# MainPower.net
KiCad netlist of a schematic drawn in Altium Designer
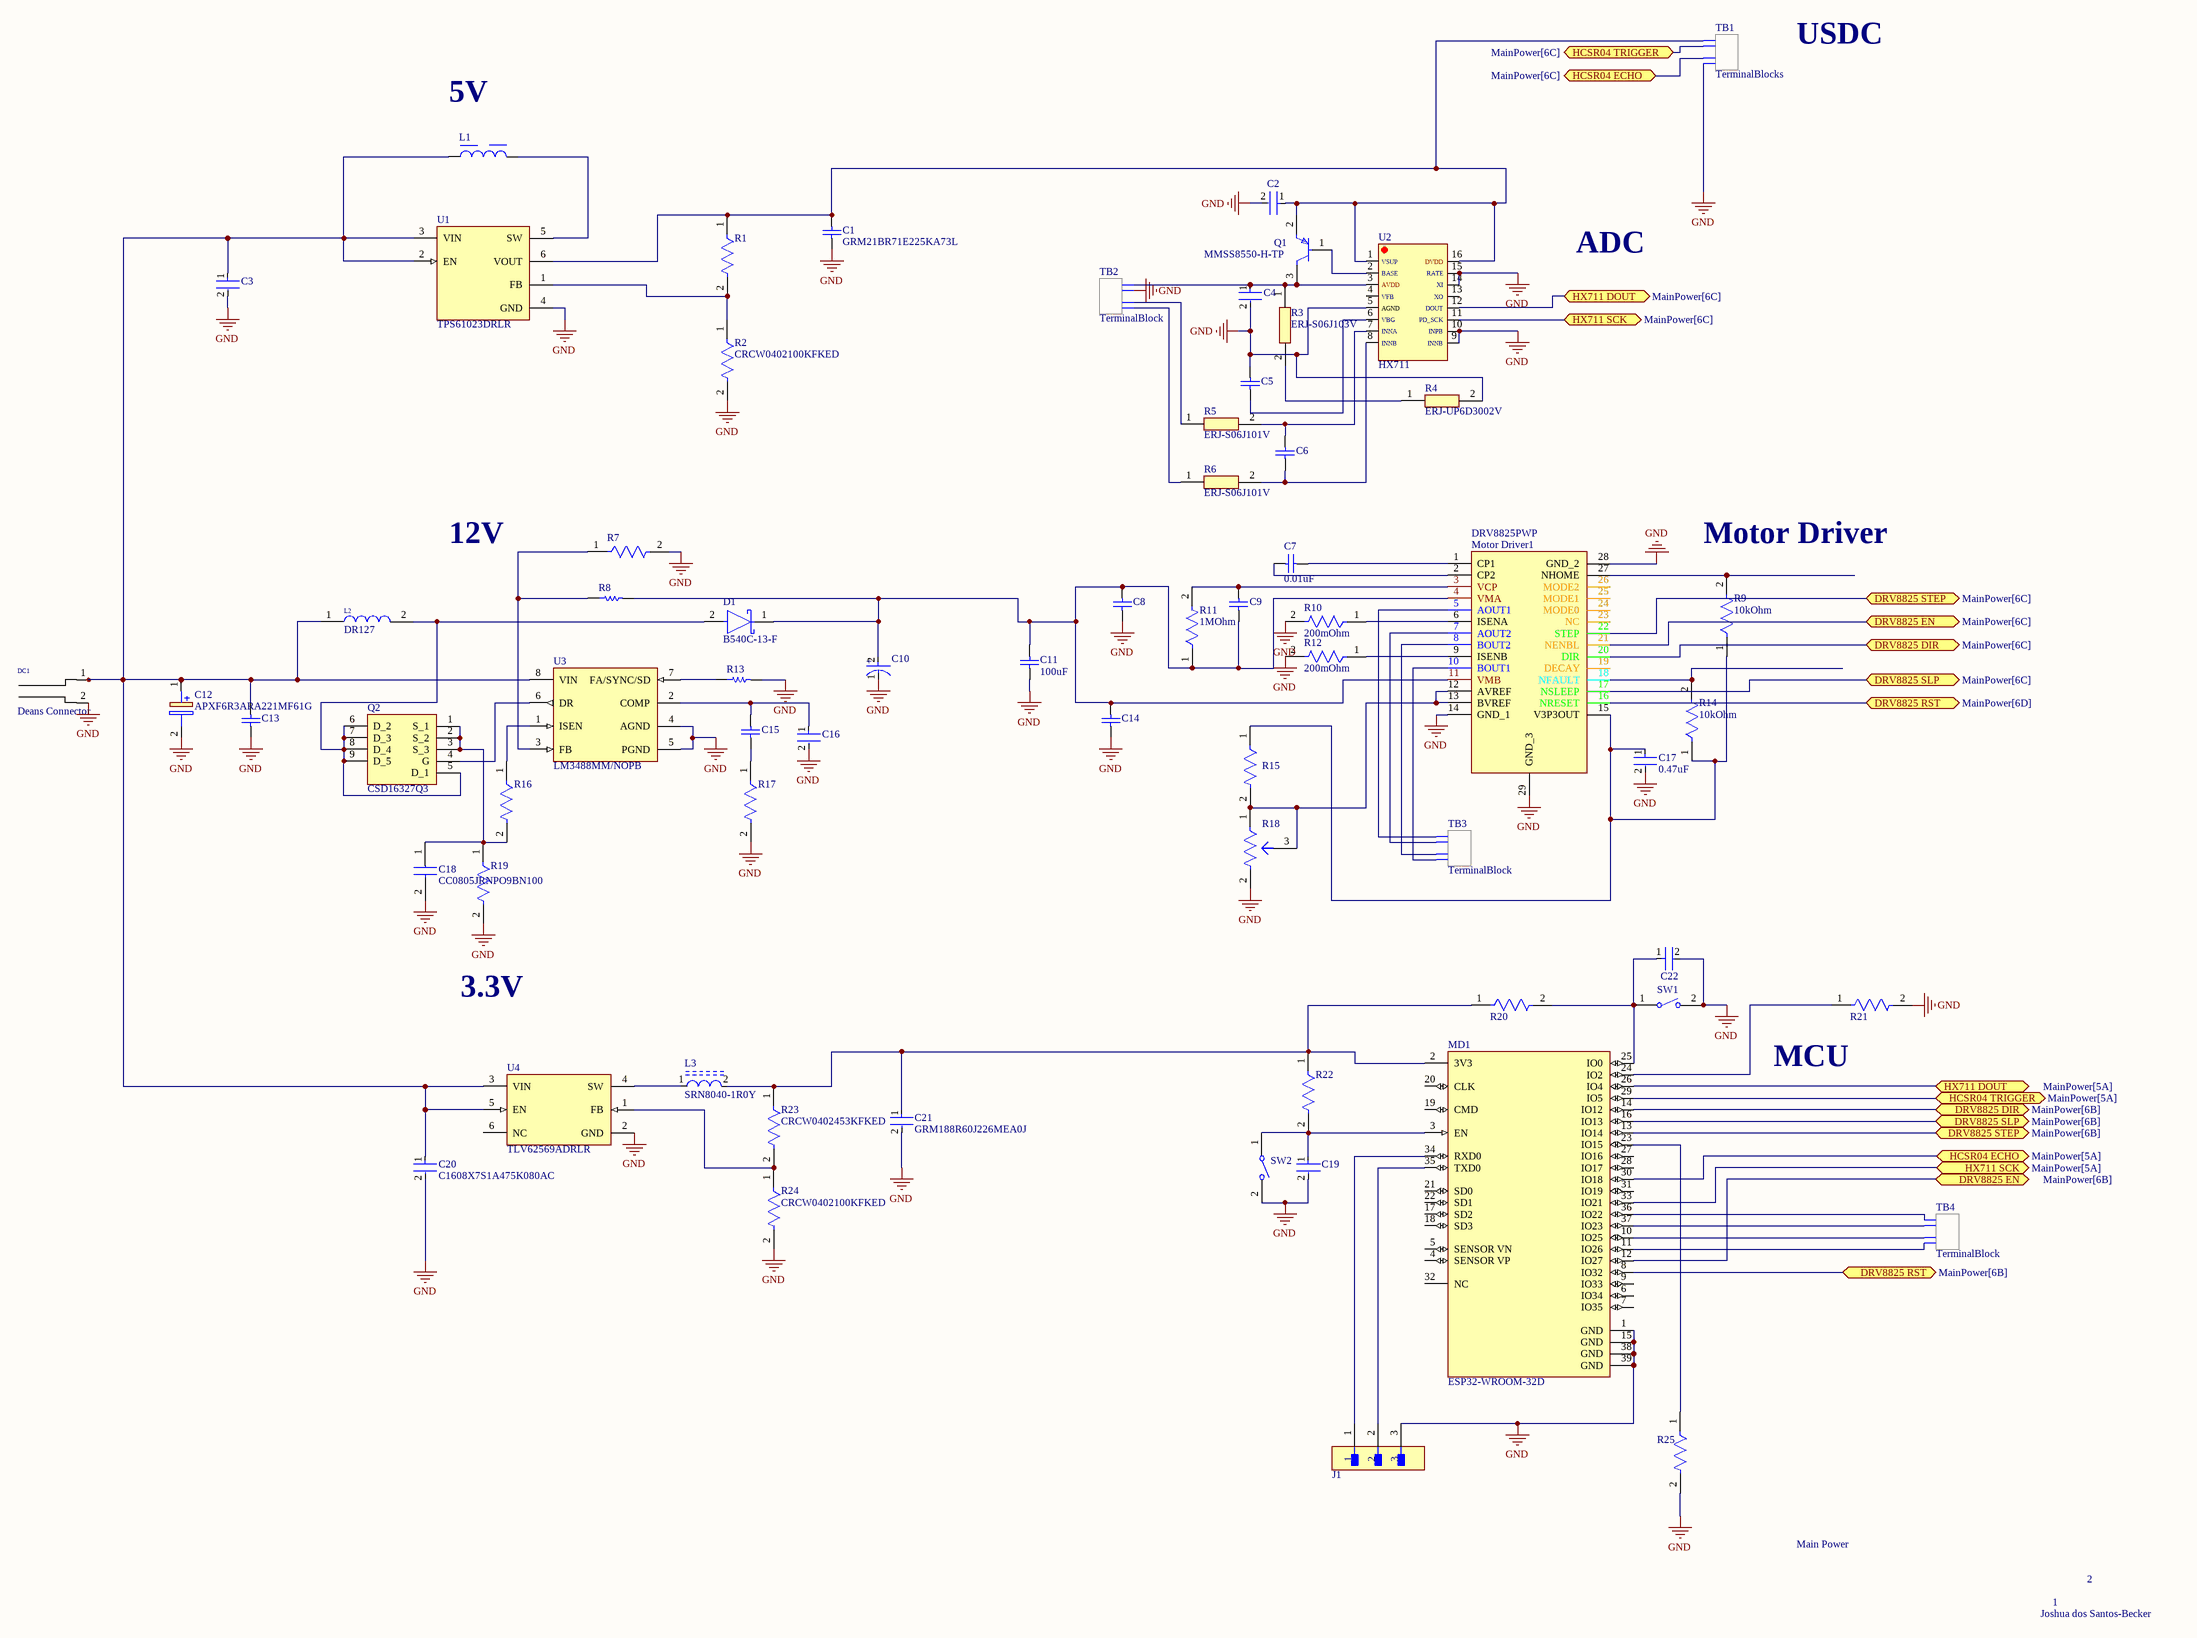
[diagram p0: MainPower.SchDoc]

(export (version "E")
  (design (tool "Eeschema 10.0.6"))
  (components
    (comp (ref "C1")
      (value "GRM21BR71E225KA73L")
      (footprint "CAPC2013X140X45NL15T25")
      (fields (field (name "MANUFACTURER") "Murata"))
      (libsource (lib "Altium Content Vault") (part "CAP"))
    )
    (comp (ref "C2")
      (value "GRM21BR61C106KE15L")
      (footprint "FP-GRM21B-0_1-IPC_C")
      (description "Chip Multilayer Ceramic Capacitors for General Purpose, 0805, 10uF, X5R, 15%, 10%, 16V")
      (fields (field (name "TOLERANCE") "10%") (field (name "VOLTAGE") "16V"))
      (libsource (lib "Altium Content Vault") (part "b4654b650e69147ec39a6b967a45e02"))
    )
    (comp (ref "C3")
      (value "C0805C106K8PACTU")
      (footprint "FP-C0805C-DG-MFG")
      (description "CAP CER 10UF 10V X5R 0805")
      (fields (field (name "TOLERANCE") "10%") (field (name "MANUFACTURER") "Kemet"))
      (libsource (lib "Altium Content Vault") (part "11868f565c42a9108669ba33697ecf6"))
    )
    (comp (ref "C4")
      (value "GRM21BR61C106KE15L")
      (footprint "FP-GRM21B-0_1-IPC_C")
      (description "Chip Multilayer Ceramic Capacitors for General Purpose, 0805, 10uF, X5R, 15%, 10%, 16V")
      (fields (field (name "TOLERANCE") "10%") (field (name "VOLTAGE") "16V"))
      (libsource (lib "Altium Content Vault") (part "b4654b650e69147ec39a6b967a45e02"))
    )
    (comp (ref "C5")
      (value "GRM033C71C104KE14J")
      (footprint "CAPC0603X33N")
      (fields (field (name "MOUSER PART NUMBER") "81-GRM033C71C104KE4J"))
      (libsource (lib "gsl") (part "0.1uF"))
    )
    (comp (ref "C6")
      (value "GRM033C71C104KE14J")
      (footprint "CAPC0603X33N")
      (fields (field (name "MOUSER PART NUMBER") "81-GRM033C71C104KE4J"))
      (libsource (lib "gsl") (part "0.1uF"))
    )
    (comp (ref "C7")
      (value "0.01uF")
      (footprint "FP-C0603-030-0_03-IPC_A")
      (description "C0603X5R1C103M030BA")
      (fields (field (name "TOLERANCE") "20%"))
      (libsource (lib "gsl") (part "0.01uF"))
    )
    (comp (ref "C8")
      (value "GRM033C71C104KE14J")
      (footprint "CAPC0603X33N")
      (fields (field (name "MOUSER PART NUMBER") "81-GRM033C71C104KE4J"))
      (libsource (lib "gsl") (part "0.1uF"))
    )
    (comp (ref "C9")
      (value "GRM033C71C104KE14J")
      (footprint "CAPC0603X33N")
      (fields (field (name "MOUSER PART NUMBER") "81-GRM033C71C104KE4J"))
      (libsource (lib "gsl") (part "0.1uF"))
    )
    (comp (ref "C10")
      (value "20SVPF390M")
      (footprint "FP-OS-CON-SMT-E12-MFG")
      (description "Conductive Polymer Aluminum Solid Capacitors (OS-CON) 390uF ±20% 20V")
      (fields (field (name "VOLTAGE") "20V") (field (name "TOLERANCE") "20%"))
      (libsource (lib "Altium Content Vault") (part "a00bbbee19879c290e62620ae7e47b1"))
    )
    (comp (ref "C11")
      (value "100uF")
      (footprint "CAPC3225X279N")
      (description "1210YD107MAT2A")
      (libsource (lib "gsl") (part "100uF"))
    )
    (comp (ref "C12")
      (value "APXF6R3ARA221MF61G")
      (footprint "SamacSys:CAPAE660X610N")
      (description "Capacitor Polarised")
      (fields (field (name "MOUSER PART NUMBER") "661-APXF6R3RA221MF61"))
      (libsource (lib "*") (part "APXF6R3ARA221MF61G"))
    )
    (comp (ref "C13")
      (value "GRM155R70J104KA01D")
      (footprint "CAPC1005X55X25NL05T10")
      (fields (field (name "MANUFACTURER") "Murata"))
      (libsource (lib "Altium Content Vault") (part "CAP"))
    )
    (comp (ref "C14")
      (value "GRM033C71C104KE14J")
      (footprint "CAPC0603X33N")
      (fields (field (name "MOUSER PART NUMBER") "81-GRM033C71C104KE4J"))
      (libsource (lib "gsl") (part "0.1uF"))
    )
    (comp (ref "C15")
      (value "GRM155R71C183KA01D")
      (footprint "CAPC1005X55X25NL05T10")
      (fields (field (name "MANUFACTURER") "Murata"))
      (libsource (lib "Altium Content Vault") (part "CAP"))
    )
    (comp (ref "C16")
      (value "CC0805KRX7R9BB102")
      (footprint "FP-CC0805-0_85-MFG")
      (description "CAP CER 1000PF 50V X7R 0805")
      (fields
        (field (name "MANUFACTURER") "Yageo")
        (field (name "OCTOPART") "https://octopart.com/cc0805krx7r9bb102-yageo-39467744")
      )
      (libsource (lib "Altium Content Vault") (part "11868f565c42a9108669ba33697ecf6"))
    )
    (comp (ref "C17")
      (value "0.47uF")
      (footprint "FP-1206-L_3_2_0_2-W_1_6_0-MFG")
      (description "12065C474K4Z2A")
      (fields (field (name "TOLERANCE") "10%"))
      (libsource (lib "Altium Content Vault") (part "b4654b650e69147ec39a6b967a45e02"))
    )
    (comp (ref "C18")
      (value "CC0805JRNPO9BN100")
      (footprint "SamacSys:CAPC2012X70N")
      (description "Capacitor")
      (fields (field (name "MOUSER PART NUMBER") "603-CC805JRNPO9BN100"))
      (libsource (lib "*") (part "CC0805JRNPO9BN100"))
    )
    (comp (ref "C19")
      (value "08055C104J4T2A")
      (footprint "FP-0805-L_2_01_0_2-W_1_25-MFG")
      (description "Automotive Ceramic Capacitor, 0805, 100nF, 5%, X7R, 15%, 50V")
      (fields (field (name "TOLERANCE") "5%"))
      (libsource (lib "Altium Content Vault") (part "02cd4be3c70576c341d710602a673aa"))
    )
    (comp (ref "C20")
      (value "C1608X7S1A475K080AC")
      (footprint "FP-C1608-080-MFG")
      (description "CAP CER 4.7UF 10V X7S 0603")
      (fields (field (name "TOLERANCE") "10%"))
      (libsource (lib "Altium Content Vault") (part "b4654b650e69147ec39a6b967a45e02"))
    )
    (comp (ref "C21")
      (value "GRM188R60J226MEA0J")
      (footprint "FP-GRM188-0_2-IPC_C")
      (description "Chip Multilayer Ceramic Capacitors for General Purpose, 0603, 22uF, X5R, 15%, 20%, 6.3V")
      (fields (field (name "TOLERANCE") "20%"))
      (libsource (lib "Altium Content Vault") (part "11868f565c42a9108669ba33697ecf6"))
    )
    (comp (ref "C22")
      (value "08055C104J4T2A")
      (footprint "FP-0805-L_2_01_0_2-W_1_25-MFG")
      (description "Automotive Ceramic Capacitor, 0805, 100nF, 5%, X7R, 15%, 50V")
      (fields (field (name "TOLERANCE") "5%"))
      (libsource (lib "Altium Content Vault") (part "02cd4be3c70576c341d710602a673aa"))
    )
    (comp (ref "D1")
      (value "B540C-13-F")
      (footprint "FP-SMC-MFG")
      (description "DIODE SCHOTTKY 40V 5A SMC")
      (fields
        (field (name "OCTOPART") "https://octopart.com/b540c-13-f-diodes+inc.-325873")
        (field (name "MANUFACTURER") "Diodes Inc.")
      )
      (libsource (lib "Altium Content Vault") (part "1d6ec82d83fb6aee721767c19dac4b9"))
    )
    (comp (ref "DC1")
      (value "Deans Connector")
      (footprint "Deans")
      (libsource (lib "gsl") (part "Deans Connector"))
    )
    (comp (ref "J1")
      (value "PREC003SAAN-RC")
      (footprint "FP-PREC003SAAN-RC-MFG")
      (description "PREC003SAAN-RC Conn Header Vert 3POS 2.54MM")
      (libsource (lib "Altium Content Vault") (part "0d3f023dd272f625e17a2be33dea85f"))
    )
    (comp (ref "L1")
      (value "74404043010A")
      (footprint "WE-LQS_4025")
      (description "74404043010A WE-LQS SMT Semi-Shielded Power Inductor")
      (libsource (lib "Altium Content Vault") (part "Inductor - 3"))
    )
    (comp (ref "L2") (value "DR127") (footprint "DR127") (libsource (lib "gsl") (part "DR127")))
    (comp (ref "L3")
      (value "SRN8040-1R0Y")
      (footprint "FP-SRN8040-MFG")
      (description "FIXED IND 1UH 7.8A 10 MOHM SMD")
      (fields (field (name "TOLERANCE") "30%"))
      (libsource (lib "Altium Content Vault") (part "faee11374f111f4f771645e57fa9eac"))
    )
    (comp (ref "MD1")
      (value "ESP32-WROOM-32D")
      (footprint "ESP32-WROOM-32D")
      (description "RX TXRX MOD WIFI SURFACE MOUNT")
      (libsource (lib "gsl") (part "ee866abf0b6c51247b7f5cdebf2f250"))
    )
    (comp (ref "Motor Driver1")
      (value "DRV8825PWP")
      (footprint "SOP65P640X120-29N")
      (fields (field (name "MOUSER PART NUMBER") "595-DRV8825PWP"))
      (libsource (lib "gsl") (part "DRV8825PWP"))
    )
    (comp (ref "Q1")
      (value "MMSS8550-H-TP")
      (footprint "FP-SOT-23-IPC_B")
      (description "TRANS PNP 25V 1.5A SOT23")
      (libsource (lib "Altium Content Vault") (part "0e8486ed3b47d9c69b8404ba87cf0f7"))
    )
    (comp (ref "Q2")
      (value "CSD16327Q3")
      (footprint "SamacSys:CSD16327Q3")
      (description "MOSFET (N-Channel)")
      (fields (field (name "MOUSER PART NUMBER") "595-CSD16327Q3"))
      (libsource (lib "*") (part "CSD16327Q3"))
    )
    (comp (ref "R1")
      (value "RC0603FR-07732KL")
      (footprint "FP-RC0603-0_55-IPC_A")
      (description "RES SMD 732K OHM 1% 1/10W 0603")
      (fields (field (name "TOLERANCE") "1%"))
      (libsource (lib "Altium Content Vault") (part "1029c3af85768c4190bb7ad29bc67b5"))
    )
    (comp (ref "R2")
      (value "CRCW0402100KFKED")
      (footprint "FP-CRCW0402-e3-IPC_C")
      (description "RES Thick Film, 100kΩ, 1%, 0.063W, 100ppm/°C, 0402")
      (fields (field (name "TOLERANCE") "1%"))
      (libsource (lib "Altium Content Vault") (part "1029c3af85768c4190bb7ad29bc67b5"))
    )
    (comp (ref "R3")
      (value "ERJ-S06J103V")
      (footprint "SamacSys:RESC2012X70N")
      (description "Resistor")
      (fields (field (name "MOUSER PART NUMBER") "667-ERJ-S06J103V"))
      (libsource (lib "*") (part "ERJ-S06J103V"))
    )
    (comp (ref "R4")
      (value "ERJ-UP6D3002V")
      (footprint "SamacSys:ERJUP6")
      (description "Resistor")
      (libsource (lib "*") (part "ERJ-UP6D3002V"))
    )
    (comp (ref "R5")
      (value "ERJ-S06J101V")
      (footprint "SamacSys:RESC2012X70N")
      (description "Resistor")
      (fields (field (name "MOUSER PART NUMBER") "667-ERJ-S06J101V"))
      (libsource (lib "*") (part "ERJ-S06J101V"))
    )
    (comp (ref "R6")
      (value "ERJ-S06J101V")
      (footprint "SamacSys:RESC2012X70N")
      (description "Resistor")
      (fields (field (name "MOUSER PART NUMBER") "667-ERJ-S06J101V"))
      (libsource (lib "*") (part "ERJ-S06J101V"))
    )
    (comp (ref "R7")
      (value "CRCW04021K00FKED")
      (footprint "FP-CRCW0402-e3-MFG")
      (description "RES Thick Film, 1kΩ, 1%, 0.063W, 100ppm/°C, 0402")
      (fields (field (name "TOLERANCE") "1%"))
      (libsource (lib "Altium Content Vault") (part "1029c3af85768c4190bb7ad29bc67b5"))
    )
    (comp (ref "R8")
      (value "CRCW04028K45FKED")
      (footprint "RESC1005X40X25LL05T05")
      (fields (field (name "MANUFACTURER") "Vishay Dale"))
      (libsource (lib "Altium Content Vault") (part "RES"))
    )
    (comp (ref "R9")
      (value "10kOhm")
      (footprint "FP-ESR10-IPC_C")
      (description "ESR10EZPD1002")
      (libsource (lib "Altium Content Vault") (part "1029c3af85768c4190bb7ad29bc67b5"))
    )
    (comp (ref "R10")
      (value "200mOhm")
      (footprint "WSL2512R2000FEA")
      (description "WSL2512R2000FEA")
      (libsource (lib "gsl") (part "200mOhm"))
    )
    (comp (ref "R11")
      (value "1MOhm")
      (footprint "RESC1005X40N")
      (description "CRCW04021M00FKEDHP")
      (libsource (lib "gsl") (part "1MOhm"))
    )
    (comp (ref "R12")
      (value "200mOhm")
      (footprint "WSL2512R2000FEA")
      (description "WSL2512R2000FEA")
      (libsource (lib "gsl") (part "200mOhm"))
    )
    (comp (ref "R13")
      (value "CRCW040226K1FKED")
      (footprint "RESC1005X40X25LL05T05")
      (fields (field (name "MANUFACTURER") "Vishay Dale"))
      (libsource (lib "Altium Content Vault") (part "RES"))
    )
    (comp (ref "R14")
      (value "10kOhm")
      (footprint "FP-ESR10-IPC_C")
      (description "ESR10EZPD1002")
      (libsource (lib "Altium Content Vault") (part "1029c3af85768c4190bb7ad29bc67b5"))
    )
    (comp (ref "R15")
      (value "~")
      (footprint "RESC1005X40N")
      (description "CRCW040250K0FKED")
      (libsource (lib "gsl") (part "50kOhm"))
    )
    (comp (ref "R16")
      (value "CRCW0402100RFKED")
      (footprint "FP-CRCW0402-e3-IPC_C")
      (description "RES Thick Film, 100Ω, 1%, 0.063W, 100ppm/°C, 0402")
      (fields (field (name "TOLERANCE") "1%"))
      (libsource (lib "Altium Content Vault") (part "1029c3af85768c4190bb7ad29bc67b5"))
    )
    (comp (ref "R17")
      (value "CRCW04025K11FKED")
      (footprint "FP-CRCW0402-e3-IPC_C")
      (description "RES Thick Film, 5.11kΩ, 1%, 0.063W, 100ppm/°C, 0402")
      (fields (field (name "TOLERANCE") "1%"))
      (libsource (lib "Altium Content Vault") (part "1029c3af85768c4190bb7ad29bc67b5"))
    )
    (comp (ref "R18")
      (value "~")
      (footprint "SMD Pot")
      (description "TC33X-2-303E Bourns")
      (libsource (lib "gsl") (part "30kPot"))
    )
    (comp (ref "R19")
      (value "PRL1632-R006-F-T1")
      (footprint "FP-PRL1632-MFG")
      (description "6 mOhms ±1% 1W Chip Resistor Wide 0612 (1632 Metric), Current Sense Thin Film")
      (fields (field (name "TOLERANCE") "1%"))
      (libsource (lib "Altium Content Vault") (part "1029c3af85768c4190bb7ad29bc67b5"))
    )
    (comp (ref "R20")
      (value "ESR10EZPD1002")
      (footprint "FP-ESR10-IPC_C")
      (description "10kΩ ±0.5% 0.4W 0805 Anti-Surge Chip Resistor AEC-Q200")
      (libsource (lib "Altium Content Vault") (part "1029c3af85768c4190bb7ad29bc67b5"))
    )
    (comp (ref "R21")
      (value "ESR10EZPD1002")
      (footprint "FP-ESR10-IPC_C")
      (description "10kΩ ±0.5% 0.4W 0805 Anti-Surge Chip Resistor AEC-Q200")
      (libsource (lib "Altium Content Vault") (part "1029c3af85768c4190bb7ad29bc67b5"))
    )
    (comp (ref "R22")
      (value "ESR10EZPD1002")
      (footprint "FP-ESR10-IPC_C")
      (description "10kΩ ±0.5% 0.4W 0805 Anti-Surge Chip Resistor AEC-Q200")
      (libsource (lib "Altium Content Vault") (part "1029c3af85768c4190bb7ad29bc67b5"))
    )
    (comp (ref "R23")
      (value "CRCW0402453KFKED")
      (footprint "FP-CRCW0402-e3-MFG")
      (description "RES Thick Film, 453kΩ, 1%, 0.063W, 100ppm/°C, 0402")
      (fields (field (name "TOLERANCE") "1%"))
      (libsource (lib "Altium Content Vault") (part "1029c3af85768c4190bb7ad29bc67b5"))
    )
    (comp (ref "R24")
      (value "CRCW0402100KFKED")
      (footprint "FP-CRCW0402-e3-IPC_C")
      (description "RES Thick Film, 100kΩ, 1%, 0.063W, 100ppm/°C, 0402")
      (fields (field (name "TOLERANCE") "1%"))
      (libsource (lib "Altium Content Vault") (part "1029c3af85768c4190bb7ad29bc67b5"))
    )
    (comp (ref "R25")
      (value "ESR10EZPD1002")
      (footprint "FP-ESR10-IPC_C")
      (description "10kΩ ±0.5% 0.4W 0805 Anti-Surge Chip Resistor AEC-Q200")
      (libsource (lib "Altium Content Vault") (part "1029c3af85768c4190bb7ad29bc67b5"))
    )
    (comp (ref "SW1")
      (value "FSMSM")
      (footprint "TECO-FSMSM-2_V")
      (description "FSMSM Push Button Switch, 50 mA, -35 to 85 degC, 2-Pin SMD, RoHS, Bulk")
      (fields (field (name "MANUFACTURER") "TE Connectivity"))
      (libsource (lib "Altium Content Vault") (part "SW-SPST-2_C"))
    )
    (comp (ref "SW2")
      (value "FSMSM")
      (footprint "TECO-FSMSM-2_V")
      (description "FSMSM Push Button Switch, 50 mA, -35 to 85 degC, 2-Pin SMD, RoHS, Bulk")
      (fields (field (name "MANUFACTURER") "TE Connectivity"))
      (libsource (lib "Altium Content Vault") (part "SW-SPST-2_C"))
    )
    (comp (ref "TB1")
      (value "TerminalBlocks")
      (footprint "PHOENIX_1725672")
      (libsource (lib "gsl") (part "TerminalBlock"))
    )
    (comp (ref "TB2")
      (value "TerminalBlock")
      (footprint "PHOENIX_1725672")
      (libsource (lib "") (part "TerminalBlock_1"))
    )
    (comp (ref "TB3")
      (value "TerminalBlock")
      (footprint "PHOENIX_1725672")
      (libsource (lib "gsl") (part "TerminalBlock"))
    )
    (comp (ref "TB4")
      (value "TerminalBlock")
      (footprint "PHOENIX_1725672")
      (libsource (lib "gsl") (part "TerminalBlock"))
    )
    (comp (ref "U1")
      (value "TPS61023DRLR")
      (footprint "FP-DRL0006A-MFG")
      (description "FINISH GOODS FOR TPS61023")
      (libsource (lib "Altium Content Vault") (part "b28b3e956a4ad07201ce69f9d09f9a8"))
    )
    (comp (ref "U2") (value "HX711") (footprint "TSOP127P600X160-16N") (libsource (lib "gsl") (part "HX711")))
    (comp (ref "U3")
      (value "LM3488MM/NOPB")
      (footprint "DGK0008A_M")
      (fields (field (name "MANUFACTURER") "Texas Instruments"))
      (libsource (lib "Altium Content Vault") (part "PM-SWREG-LM3488-8"))
    )
    (comp (ref "U4")
      (value "TLV62569ADRLR")
      (footprint "FP-DRL0006A-MFG")
      (description "IC REG BUCK ADJ 2A SOT563")
      (libsource (lib "Altium Content Vault") (part "c065b8f3016c1e0e14a773cb518fcf3"))
    )
  )
  (nets
    (net (code "1") (name "/DRV8825 DIR") (class "Default")
      (node (ref "MD1") (pin "14") (pinfunction "IO12_14") (pintype "bidirectional"))
      (node (ref "Motor Driver1") (pin "20") (pinfunction "DIR_20") (pintype "passive"))
    )
    (net (code "2") (name "/DRV8825 EN") (class "Default")
      (node (ref "MD1") (pin "12") (pinfunction "IO27_12") (pintype "bidirectional"))
      (node (ref "Motor Driver1") (pin "21") (pinfunction "NENBL_21") (pintype "passive"))
    )
    (net (code "3") (name "/DRV8825 RST") (class "Default")
      (node (ref "MD1") (pin "8") (pinfunction "IO32_8") (pintype "bidirectional"))
      (node (ref "Motor Driver1") (pin "16") (pinfunction "NRESET_16") (pintype "passive"))
    )
    (net (code "4") (name "/DRV8825 SLP") (class "Default")
      (node (ref "MD1") (pin "16") (pinfunction "IO13_16") (pintype "bidirectional"))
      (node (ref "Motor Driver1") (pin "17") (pinfunction "NSLEEP_17") (pintype "passive"))
    )
    (net (code "5") (name "/DRV8825 STEP") (class "Default")
      (node (ref "MD1") (pin "13") (pinfunction "IO14_13") (pintype "bidirectional"))
      (node (ref "Motor Driver1") (pin "22") (pinfunction "STEP_22") (pintype "passive"))
    )
    (net (code "6") (name "/HCSR04 ECHO") (class "Default")
      (node (ref "MD1") (pin "30") (pinfunction "IO18_30") (pintype "bidirectional"))
      (node (ref "TB1") (pin "3") (pinfunction "3_3") (pintype "passive"))
    )
    (net (code "7") (name "/HCSR04 TRIGGER") (class "Default")
      (node (ref "MD1") (pin "29") (pinfunction "IO5_29") (pintype "bidirectional"))
      (node (ref "TB1") (pin "2") (pinfunction "2_2") (pintype "passive"))
    )
    (net (code "8") (name "/HX711 DOUT") (class "Default")
      (node (ref "MD1") (pin "26") (pinfunction "IO4_26") (pintype "bidirectional"))
      (node (ref "U2") (pin "12") (pinfunction "12_12") (pintype "passive"))
    )
    (net (code "9") (name "/HX711 SCK") (class "Default")
      (node (ref "MD1") (pin "33") (pinfunction "IO21_33") (pintype "bidirectional"))
      (node (ref "U2") (pin "11") (pinfunction "11_11") (pintype "passive"))
    )
    (net (code "10") (name "GND") (class "Default")
      (node (ref "C1") (pin "2") (pinfunction "2_2") (pintype "passive"))
      (node (ref "C10") (pin "1") (pinfunction "C_1") (pintype "passive"))
      (node (ref "C11") (pin "1") (pinfunction "1_1") (pintype "passive"))
      (node (ref "C12") (pin "2") (pinfunction "-_2") (pintype "passive"))
      (node (ref "C13") (pin "2") (pinfunction "2_2") (pintype "passive"))
      (node (ref "C14") (pin "1") (pinfunction "1_1") (pintype "passive"))
      (node (ref "C16") (pin "2") (pinfunction "2_2") (pintype "passive"))
      (node (ref "C17") (pin "2") (pinfunction "2_2") (pintype "passive"))
      (node (ref "C18") (pin "2") (pinfunction "2_2") (pintype "passive"))
      (node (ref "C19") (pin "2") (pinfunction "2_2") (pintype "passive"))
      (node (ref "C2") (pin "2") (pinfunction "2_2") (pintype "passive"))
      (node (ref "C20") (pin "2") (pinfunction "2_2") (pintype "passive"))
      (node (ref "C21") (pin "2") (pinfunction "2_2") (pintype "passive"))
      (node (ref "C22") (pin "2") (pinfunction "2_2") (pintype "passive"))
      (node (ref "C3") (pin "2") (pinfunction "2_2") (pintype "passive"))
      (node (ref "C4") (pin "2") (pinfunction "2_2") (pintype "passive"))
      (node (ref "C5") (pin "2") (pinfunction "2_2") (pintype "passive"))
      (node (ref "C8") (pin "1") (pinfunction "1_1") (pintype "passive"))
      (node (ref "DC1") (pin "2") (pinfunction "2_2") (pintype "passive"))
      (node (ref "J1") (pin "3") (pinfunction "3_3") (pintype "passive"))
      (node (ref "MD1") (pin "1") (pinfunction "GND_1") (pintype "power_in"))
      (node (ref "MD1") (pin "15") (pinfunction "GND_15") (pintype "power_in"))
      (node (ref "MD1") (pin "38") (pinfunction "GND_38") (pintype "power_in"))
      (node (ref "MD1") (pin "39") (pinfunction "GND_39") (pintype "power_in"))
      (node (ref "Motor Driver1") (pin "14") (pinfunction "GND_1_14") (pintype "passive"))
      (node (ref "Motor Driver1") (pin "28") (pinfunction "GND_2_28") (pintype "passive"))
      (node (ref "Motor Driver1") (pin "29") (pinfunction "GND_3_29") (pintype "passive"))
      (node (ref "R10") (pin "2") (pinfunction "2_2") (pintype "passive"))
      (node (ref "R12") (pin "2") (pinfunction "2_2") (pintype "passive"))
      (node (ref "R13") (pin "2") (pinfunction "2_2") (pintype "passive"))
      (node (ref "R17") (pin "2") (pinfunction "2_2") (pintype "passive"))
      (node (ref "R18") (pin "2") (pinfunction "2_2") (pintype "passive"))
      (node (ref "R19") (pin "2") (pinfunction "2_2") (pintype "passive"))
      (node (ref "R2") (pin "2") (pinfunction "2_2") (pintype "passive"))
      (node (ref "R21") (pin "2") (pinfunction "2_2") (pintype "passive"))
      (node (ref "R24") (pin "2") (pinfunction "2_2") (pintype "passive"))
      (node (ref "R25") (pin "2") (pinfunction "2_2") (pintype "passive"))
      (node (ref "R4") (pin "2") (pinfunction "2_2") (pintype "passive"))
      (node (ref "R7") (pin "2") (pinfunction "2_2") (pintype "passive"))
      (node (ref "SW1") (pin "2") (pinfunction "2_2") (pintype "passive"))
      (node (ref "SW2") (pin "2") (pinfunction "2_2") (pintype "passive"))
      (node (ref "TB1") (pin "4") (pinfunction "4_4") (pintype "passive"))
      (node (ref "TB2") (pin "3") (pinfunction "3_3") (pintype "passive"))
      (node (ref "U1") (pin "4") (pinfunction "GND_4") (pintype "power_in"))
      (node (ref "U2") (pin "10") (pinfunction "10_10") (pintype "passive"))
      (node (ref "U2") (pin "14") (pinfunction "14_14") (pintype "passive"))
      (node (ref "U2") (pin "15") (pinfunction "15_15") (pintype "passive"))
      (node (ref "U2") (pin "5") (pinfunction "5_5") (pintype "passive"))
      (node (ref "U2") (pin "9") (pinfunction "9_9") (pintype "passive"))
      (node (ref "U3") (pin "4") (pinfunction "AGND_4") (pintype "power_in"))
      (node (ref "U3") (pin "5") (pinfunction "PGND_5") (pintype "power_in"))
      (node (ref "U4") (pin "2") (pinfunction "GND_2") (pintype "power_in"))
    )
    (net (code "11") (name "Net-(C5-Pad1)") (class "Default")
      (node (ref "C5") (pin "1") (pinfunction "1_1") (pintype "passive"))
      (node (ref "U2") (pin "6") (pinfunction "6_6") (pintype "passive"))
    )
    (net (code "12") (name "Net-(C6-Pad1)") (class "Default")
      (node (ref "C6") (pin "1") (pinfunction "1_1") (pintype "passive"))
      (node (ref "R6") (pin "2") (pinfunction "2_2") (pintype "passive"))
      (node (ref "U2") (pin "8") (pinfunction "8_8") (pintype "passive"))
    )
    (net (code "13") (name "Net-(C6-Pad2)") (class "Default")
      (node (ref "C6") (pin "2") (pinfunction "2_2") (pintype "passive"))
      (node (ref "R5") (pin "2") (pinfunction "2_2") (pintype "passive"))
      (node (ref "U2") (pin "7") (pinfunction "7_7") (pintype "passive"))
    )
    (net (code "14") (name "Net-(C10-A)") (class "Default")
      (node (ref "C10") (pin "2") (pinfunction "A_2") (pintype "passive"))
      (node (ref "C11") (pin "2") (pinfunction "2_2") (pintype "passive"))
      (node (ref "C14") (pin "2") (pinfunction "2_2") (pintype "passive"))
      (node (ref "C8") (pin "2") (pinfunction "2_2") (pintype "passive"))
      (node (ref "C9") (pin "1") (pinfunction "1_1") (pintype "passive"))
      (node (ref "D1") (pin "1") (pinfunction "C_1") (pintype "passive"))
      (node (ref "Motor Driver1") (pin "11") (pinfunction "VMB_11") (pintype "passive"))
      (node (ref "Motor Driver1") (pin "4") (pinfunction "VMA_4") (pintype "passive"))
      (node (ref "R11") (pin "1") (pinfunction "1_1") (pintype "passive"))
      (node (ref "R8") (pin "2") (pinfunction "2_2") (pintype "passive"))
    )
    (net (code "15") (name "Net-(C12-+)") (class "Default")
      (node (ref "C12") (pin "1") (pinfunction "+_1") (pintype "passive"))
      (node (ref "C13") (pin "1") (pinfunction "1_1") (pintype "passive"))
      (node (ref "C20") (pin "1") (pinfunction "1_1") (pintype "passive"))
      (node (ref "C3") (pin "1") (pinfunction "1_1") (pintype "passive"))
      (node (ref "DC1") (pin "1") (pinfunction "1_1") (pintype "passive"))
      (node (ref "L1") (pin "1") (pinfunction "1_1") (pintype "passive"))
      (node (ref "L2") (pin "1") (pinfunction "1_1") (pintype "passive"))
      (node (ref "U1") (pin "2") (pinfunction "EN_2") (pintype "input"))
      (node (ref "U1") (pin "3") (pinfunction "VIN_3") (pintype "power_in"))
      (node (ref "U3") (pin "8") (pinfunction "VIN_8") (pintype "power_in"))
      (node (ref "U4") (pin "3") (pinfunction "VIN_3") (pintype "power_in"))
      (node (ref "U4") (pin "5") (pinfunction "EN_5") (pintype "input"))
    )
    (net (code "16") (name "Net-(C15-Pad2)") (class "Default")
      (node (ref "C15") (pin "2") (pinfunction "2_2") (pintype "passive"))
      (node (ref "R17") (pin "1") (pinfunction "1_1") (pintype "passive"))
    )
    (net (code "17") (name "Net-(D1-A)") (class "Default")
      (node (ref "D1") (pin "2") (pinfunction "A_2") (pintype "passive"))
      (node (ref "L2") (pin "2") (pinfunction "2_2") (pintype "passive"))
      (node (ref "Q2") (pin "5") (pinfunction "D_1_5") (pintype "passive"))
      (node (ref "Q2") (pin "6") (pinfunction "D_2_6") (pintype "passive"))
      (node (ref "Q2") (pin "7") (pinfunction "D_3_7") (pintype "passive"))
      (node (ref "Q2") (pin "8") (pinfunction "D_4_8") (pintype "passive"))
      (node (ref "Q2") (pin "9") (pinfunction "D_5_9") (pintype "passive"))
    )
    (net (code "18") (name "Net-(MD1-3V3)") (class "Default")
      (node (ref "C21") (pin "1") (pinfunction "1_1") (pintype "passive"))
      (node (ref "L3") (pin "2") (pinfunction "2_2") (pintype "passive"))
      (node (ref "MD1") (pin "2") (pinfunction "3V3_2") (pintype "power_in"))
      (node (ref "R20") (pin "1") (pinfunction "1_1") (pintype "passive"))
      (node (ref "R22") (pin "1") (pinfunction "1_1") (pintype "passive"))
      (node (ref "R23") (pin "1") (pinfunction "1_1") (pintype "passive"))
    )
    (net (code "19") (name "Net-(MD1-EN)") (class "Default")
      (node (ref "C19") (pin "1") (pinfunction "1_1") (pintype "passive"))
      (node (ref "MD1") (pin "3") (pinfunction "EN_3") (pintype "input"))
      (node (ref "R22") (pin "2") (pinfunction "2_2") (pintype "passive"))
      (node (ref "SW2") (pin "1") (pinfunction "1_1") (pintype "passive"))
    )
    (net (code "20") (name "Net-(MD1-IO0)") (class "Default")
      (node (ref "C22") (pin "1") (pinfunction "1_1") (pintype "passive"))
      (node (ref "MD1") (pin "25") (pinfunction "IO0_25") (pintype "bidirectional"))
      (node (ref "R20") (pin "2") (pinfunction "2_2") (pintype "passive"))
      (node (ref "SW1") (pin "1") (pinfunction "1_1") (pintype "passive"))
    )
    (net (code "21") (name "Net-(MD1-IO2)") (class "Default")
      (node (ref "MD1") (pin "24") (pinfunction "IO2_24") (pintype "bidirectional"))
      (node (ref "R21") (pin "1") (pinfunction "1_1") (pintype "passive"))
    )
    (net (code "22") (name "Net-(MD1-IO15)") (class "Default")
      (node (ref "MD1") (pin "23") (pinfunction "IO15_23") (pintype "bidirectional"))
      (node (ref "R25") (pin "1") (pinfunction "1_1") (pintype "passive"))
    )
    (net (code "23") (name "Net-(MD1-IO22)") (class "Default")
      (node (ref "MD1") (pin "36") (pinfunction "IO22_36") (pintype "bidirectional"))
      (node (ref "TB4") (pin "1") (pinfunction "1_1") (pintype "passive"))
    )
    (net (code "24") (name "Net-(MD1-IO23)") (class "Default")
      (node (ref "MD1") (pin "37") (pinfunction "IO23_37") (pintype "bidirectional"))
      (node (ref "TB4") (pin "2") (pinfunction "2_2") (pintype "passive"))
    )
    (net (code "25") (name "Net-(MD1-IO25)") (class "Default")
      (node (ref "MD1") (pin "10") (pinfunction "IO25_10") (pintype "bidirectional"))
      (node (ref "TB4") (pin "3") (pinfunction "3_3") (pintype "passive"))
    )
    (net (code "26") (name "Net-(MD1-IO26)") (class "Default")
      (node (ref "MD1") (pin "11") (pinfunction "IO26_11") (pintype "bidirectional"))
      (node (ref "TB4") (pin "4") (pinfunction "4_4") (pintype "passive"))
    )
    (net (code "27") (name "Net-(MD1-RXD0)") (class "Default")
      (node (ref "J1") (pin "1") (pinfunction "1_1") (pintype "passive"))
      (node (ref "MD1") (pin "34") (pinfunction "RXD0_34") (pintype "bidirectional"))
    )
    (net (code "28") (name "Net-(MD1-TXD0)") (class "Default")
      (node (ref "J1") (pin "2") (pinfunction "2_2") (pintype "passive"))
      (node (ref "MD1") (pin "35") (pinfunction "TXD0_35") (pintype "bidirectional"))
    )
    (net (code "29") (name "Net-(Motor Driver1-AOUT1)") (class "Default")
      (node (ref "Motor Driver1") (pin "5") (pinfunction "AOUT1_5") (pintype "passive"))
      (node (ref "TB3") (pin "1") (pinfunction "1_1") (pintype "passive"))
    )
    (net (code "30") (name "Net-(Motor Driver1-AOUT2)") (class "Default")
      (node (ref "Motor Driver1") (pin "7") (pinfunction "AOUT2_7") (pintype "passive"))
      (node (ref "TB3") (pin "2") (pinfunction "2_2") (pintype "passive"))
    )
    (net (code "31") (name "Net-(Motor Driver1-AVREF)") (class "Default")
      (node (ref "Motor Driver1") (pin "12") (pinfunction "AVREF_12") (pintype "passive"))
      (node (ref "Motor Driver1") (pin "13") (pinfunction "BVREF_13") (pintype "passive"))
      (node (ref "R15") (pin "2") (pinfunction "2_2") (pintype "passive"))
      (node (ref "R18") (pin "1") (pinfunction "1_1") (pintype "passive"))
      (node (ref "R18") (pin "3") (pinfunction "3_3") (pintype "passive"))
    )
    (net (code "32") (name "Net-(Motor Driver1-BOUT1)") (class "Default")
      (node (ref "Motor Driver1") (pin "10") (pinfunction "BOUT1_10") (pintype "passive"))
      (node (ref "TB3") (pin "4") (pinfunction "4_4") (pintype "passive"))
    )
    (net (code "33") (name "Net-(Motor Driver1-BOUT2)") (class "Default")
      (node (ref "Motor Driver1") (pin "8") (pinfunction "BOUT2_8") (pintype "passive"))
      (node (ref "TB3") (pin "3") (pinfunction "3_3") (pintype "passive"))
    )
    (net (code "34") (name "Net-(Motor Driver1-CP1)") (class "Default")
      (node (ref "C7") (pin "1") (pinfunction "1_1") (pintype "passive"))
      (node (ref "Motor Driver1") (pin "1") (pinfunction "CP1_1") (pintype "passive"))
    )
    (net (code "35") (name "Net-(Motor Driver1-CP2)") (class "Default")
      (node (ref "C7") (pin "2") (pinfunction "2_2") (pintype "passive"))
      (node (ref "Motor Driver1") (pin "2") (pinfunction "CP2_2") (pintype "passive"))
    )
    (net (code "36") (name "Net-(Motor Driver1-ISENA)") (class "Default")
      (node (ref "Motor Driver1") (pin "6") (pinfunction "ISENA_6") (pintype "passive"))
      (node (ref "R10") (pin "1") (pinfunction "1_1") (pintype "passive"))
    )
    (net (code "37") (name "Net-(Motor Driver1-ISENB)") (class "Default")
      (node (ref "Motor Driver1") (pin "9") (pinfunction "ISENB_9") (pintype "passive"))
      (node (ref "R12") (pin "1") (pinfunction "1_1") (pintype "passive"))
    )
    (net (code "38") (name "Net-(Motor Driver1-NFAULT)") (class "Default")
      (node (ref "Motor Driver1") (pin "18") (pinfunction "NFAULT_18") (pintype "passive"))
      (node (ref "R14") (pin "2") (pinfunction "2_2") (pintype "passive"))
    )
    (net (code "39") (name "Net-(Motor Driver1-NHOME)") (class "Default")
      (node (ref "Motor Driver1") (pin "27") (pinfunction "NHOME_27") (pintype "passive"))
      (node (ref "R9") (pin "2") (pinfunction "2_2") (pintype "passive"))
    )
    (net (code "40") (name "Net-(Motor Driver1-V3P3OUT)") (class "Default")
      (node (ref "C17") (pin "1") (pinfunction "1_1") (pintype "passive"))
      (node (ref "Motor Driver1") (pin "15") (pinfunction "V3P3OUT_15") (pintype "passive"))
      (node (ref "R14") (pin "1") (pinfunction "1_1") (pintype "passive"))
      (node (ref "R15") (pin "1") (pinfunction "1_1") (pintype "passive"))
      (node (ref "R9") (pin "1") (pinfunction "1_1") (pintype "passive"))
    )
    (net (code "41") (name "Net-(Motor Driver1-VCP)") (class "Default")
      (node (ref "C9") (pin "2") (pinfunction "2_2") (pintype "passive"))
      (node (ref "Motor Driver1") (pin "3") (pinfunction "VCP_3") (pintype "passive"))
      (node (ref "R11") (pin "2") (pinfunction "2_2") (pintype "passive"))
    )
    (net (code "42") (name "Net-(Q1-B)") (class "Default")
      (node (ref "Q1") (pin "1") (pinfunction "B_1") (pintype "passive"))
      (node (ref "U2") (pin "2") (pinfunction "2_2") (pintype "passive"))
    )
    (net (code "43") (name "Net-(Q1-C)") (class "Default")
      (node (ref "C4") (pin "1") (pinfunction "1_1") (pintype "passive"))
      (node (ref "Q1") (pin "3") (pinfunction "C_3") (pintype "passive"))
      (node (ref "R3") (pin "1") (pinfunction "1_1") (pintype "passive"))
      (node (ref "TB2") (pin "4") (pinfunction "4_4") (pintype "passive"))
      (node (ref "U2") (pin "3") (pinfunction "3_3") (pintype "passive"))
    )
    (net (code "44") (name "Net-(Q1-E)") (class "Default")
      (node (ref "C1") (pin "1") (pinfunction "1_1") (pintype "passive"))
      (node (ref "C2") (pin "1") (pinfunction "1_1") (pintype "passive"))
      (node (ref "Q1") (pin "2") (pinfunction "E_2") (pintype "passive"))
      (node (ref "R1") (pin "1") (pinfunction "1_1") (pintype "passive"))
      (node (ref "TB1") (pin "1") (pinfunction "1_1") (pintype "passive"))
      (node (ref "U1") (pin "6") (pinfunction "VOUT_6") (pintype "power_in"))
      (node (ref "U2") (pin "1") (pinfunction "1_1") (pintype "passive"))
      (node (ref "U2") (pin "16") (pinfunction "16_16") (pintype "passive"))
    )
    (net (code "45") (name "Net-(Q2-G)") (class "Default")
      (node (ref "Q2") (pin "4") (pinfunction "G_4") (pintype "passive"))
      (node (ref "U3") (pin "6") (pinfunction "DR_6") (pintype "output"))
    )
    (net (code "46") (name "Net-(Q2-S_1)") (class "Default")
      (node (ref "C18") (pin "1") (pinfunction "1_1") (pintype "passive"))
      (node (ref "Q2") (pin "1") (pinfunction "S_1_1") (pintype "passive"))
      (node (ref "Q2") (pin "2") (pinfunction "S_2_2") (pintype "passive"))
      (node (ref "Q2") (pin "3") (pinfunction "S_3_3") (pintype "passive"))
      (node (ref "R16") (pin "2") (pinfunction "2_2") (pintype "passive"))
      (node (ref "R19") (pin "1") (pinfunction "1_1") (pintype "passive"))
    )
    (net (code "47") (name "Net-(R3-Pad2)") (class "Default")
      (node (ref "R3") (pin "2") (pinfunction "2_2") (pintype "passive"))
      (node (ref "R4") (pin "1") (pinfunction "1_1") (pintype "passive"))
    )
    (net (code "48") (name "Net-(R5-Pad1)") (class "Default")
      (node (ref "R5") (pin "1") (pinfunction "1_1") (pintype "passive"))
      (node (ref "TB2") (pin "2") (pinfunction "2_2") (pintype "passive"))
    )
    (net (code "49") (name "Net-(R6-Pad1)") (class "Default")
      (node (ref "R6") (pin "1") (pinfunction "1_1") (pintype "passive"))
      (node (ref "TB2") (pin "1") (pinfunction "1_1") (pintype "passive"))
    )
    (net (code "50") (name "Net-(U1-FB)") (class "Default")
      (node (ref "R1") (pin "2") (pinfunction "2_2") (pintype "passive"))
      (node (ref "R2") (pin "1") (pinfunction "1_1") (pintype "passive"))
      (node (ref "U1") (pin "1") (pinfunction "FB_1") (pintype "passive"))
    )
    (net (code "51") (name "Net-(U1-SW)") (class "Default")
      (node (ref "L1") (pin "2") (pinfunction "2_2") (pintype "passive"))
      (node (ref "U1") (pin "5") (pinfunction "SW_5") (pintype "passive"))
    )
    (net (code "52") (name "Net-(U3-COMP)") (class "Default")
      (node (ref "C15") (pin "1") (pinfunction "1_1") (pintype "passive"))
      (node (ref "C16") (pin "1") (pinfunction "1_1") (pintype "passive"))
      (node (ref "U3") (pin "2") (pinfunction "COMP_2") (pintype "passive"))
    )
    (net (code "53") (name "Net-(U3-FA{slash}SYNC{slash}SD)") (class "Default")
      (node (ref "R13") (pin "1") (pinfunction "1_1") (pintype "passive"))
      (node (ref "U3") (pin "7") (pinfunction "FA/SYNC/SD_7") (pintype "input"))
    )
    (net (code "54") (name "Net-(U3-FB)") (class "Default")
      (node (ref "R7") (pin "1") (pinfunction "1_1") (pintype "passive"))
      (node (ref "R8") (pin "1") (pinfunction "1_1") (pintype "passive"))
      (node (ref "U3") (pin "3") (pinfunction "FB_3") (pintype "input"))
    )
    (net (code "55") (name "Net-(U3-ISEN)") (class "Default")
      (node (ref "R16") (pin "1") (pinfunction "1_1") (pintype "passive"))
      (node (ref "U3") (pin "1") (pinfunction "ISEN_1") (pintype "input"))
    )
    (net (code "56") (name "Net-(U4-FB)") (class "Default")
      (node (ref "R23") (pin "2") (pinfunction "2_2") (pintype "passive"))
      (node (ref "R24") (pin "1") (pinfunction "1_1") (pintype "passive"))
      (node (ref "U4") (pin "1") (pinfunction "FB_1") (pintype "input"))
    )
    (net (code "57") (name "Net-(U4-SW)") (class "Default")
      (node (ref "L3") (pin "1") (pinfunction "1_1") (pintype "passive"))
      (node (ref "U4") (pin "4") (pinfunction "SW_4") (pintype "passive"))
    )
    (net (code "58") (name "unconnected-(MD1-CLK-Pad20)") (class "Default")
      (node (ref "MD1") (pin "20") (pinfunction "CLK_20") (pintype "bidirectional"))
    )
    (net (code "59") (name "unconnected-(MD1-CMD-Pad19)") (class "Default")
      (node (ref "MD1") (pin "19") (pinfunction "CMD_19") (pintype "bidirectional"))
    )
    (net (code "60") (name "unconnected-(MD1-IO16-Pad27)") (class "Default")
      (node (ref "MD1") (pin "27") (pinfunction "IO16_27") (pintype "bidirectional"))
    )
    (net (code "61") (name "unconnected-(MD1-IO17-Pad28)") (class "Default")
      (node (ref "MD1") (pin "28") (pinfunction "IO17_28") (pintype "bidirectional"))
    )
    (net (code "62") (name "unconnected-(MD1-IO19-Pad31)") (class "Default")
      (node (ref "MD1") (pin "31") (pinfunction "IO19_31") (pintype "bidirectional"))
    )
    (net (code "63") (name "unconnected-(MD1-IO33-Pad9)") (class "Default")
      (node (ref "MD1") (pin "9") (pinfunction "IO33_9") (pintype "bidirectional"))
    )
    (net (code "64") (name "unconnected-(MD1-IO34-Pad6)") (class "Default")
      (node (ref "MD1") (pin "6") (pinfunction "IO34_6") (pintype "bidirectional"))
    )
    (net (code "65") (name "unconnected-(MD1-IO35-Pad7)") (class "Default")
      (node (ref "MD1") (pin "7") (pinfunction "IO35_7") (pintype "bidirectional"))
    )
    (net (code "66") (name "unconnected-(MD1-NC-Pad32)") (class "Default")
      (node (ref "MD1") (pin "32") (pinfunction "NC_32") (pintype "passive"))
    )
    (net (code "67") (name "unconnected-(MD1-SD0-Pad21)") (class "Default")
      (node (ref "MD1") (pin "21") (pinfunction "SD0_21") (pintype "bidirectional"))
    )
    (net (code "68") (name "unconnected-(MD1-SD1-Pad22)") (class "Default")
      (node (ref "MD1") (pin "22") (pinfunction "SD1_22") (pintype "bidirectional"))
    )
    (net (code "69") (name "unconnected-(MD1-SD2-Pad17)") (class "Default")
      (node (ref "MD1") (pin "17") (pinfunction "SD2_17") (pintype "bidirectional"))
    )
    (net (code "70") (name "unconnected-(MD1-SD3-Pad18)") (class "Default")
      (node (ref "MD1") (pin "18") (pinfunction "SD3_18") (pintype "bidirectional"))
    )
    (net (code "71") (name "unconnected-(MD1-SENSOR_VN-Pad5)") (class "Default")
      (node (ref "MD1") (pin "5") (pinfunction "SENSOR_VN_5") (pintype "bidirectional"))
    )
    (net (code "72") (name "unconnected-(MD1-SENSOR_VP-Pad4)") (class "Default")
      (node (ref "MD1") (pin "4") (pinfunction "SENSOR_VP_4") (pintype "bidirectional"))
    )
    (net (code "73") (name "unconnected-(Motor Driver1-DECAY-Pad19)") (class "Default")
      (node (ref "Motor Driver1") (pin "19") (pinfunction "DECAY_19") (pintype "passive"))
    )
    (net (code "74") (name "unconnected-(Motor Driver1-MODE0-Pad24)") (class "Default")
      (node (ref "Motor Driver1") (pin "24") (pinfunction "MODE0_24") (pintype "passive"))
    )
    (net (code "75") (name "unconnected-(Motor Driver1-MODE1-Pad25)") (class "Default")
      (node (ref "Motor Driver1") (pin "25") (pinfunction "MODE1_25") (pintype "passive"))
    )
    (net (code "76") (name "unconnected-(Motor Driver1-MODE2-Pad26)") (class "Default")
      (node (ref "Motor Driver1") (pin "26") (pinfunction "MODE2_26") (pintype "passive"))
    )
    (net (code "77") (name "unconnected-(Motor Driver1-NC-Pad23)") (class "Default")
      (node (ref "Motor Driver1") (pin "23") (pinfunction "NC_23") (pintype "passive"))
    )
    (net (code "78") (name "unconnected-(U2-Pad4)") (class "Default")
      (node (ref "U2") (pin "4") (pinfunction "4_4") (pintype "passive"))
    )
    (net (code "79") (name "unconnected-(U2-Pad13)") (class "Default")
      (node (ref "U2") (pin "13") (pinfunction "13_13") (pintype "passive"))
    )
    (net (code "80") (name "unconnected-(U4-NC-Pad6)") (class "Default")
      (node (ref "U4") (pin "6") (pinfunction "NC_6") (pintype "passive"))
    )
  )
)
